# Ad_Hoc_Radio_Node_2005_v2.net
KiCad netlist of a schematic drawn in Altium Designer
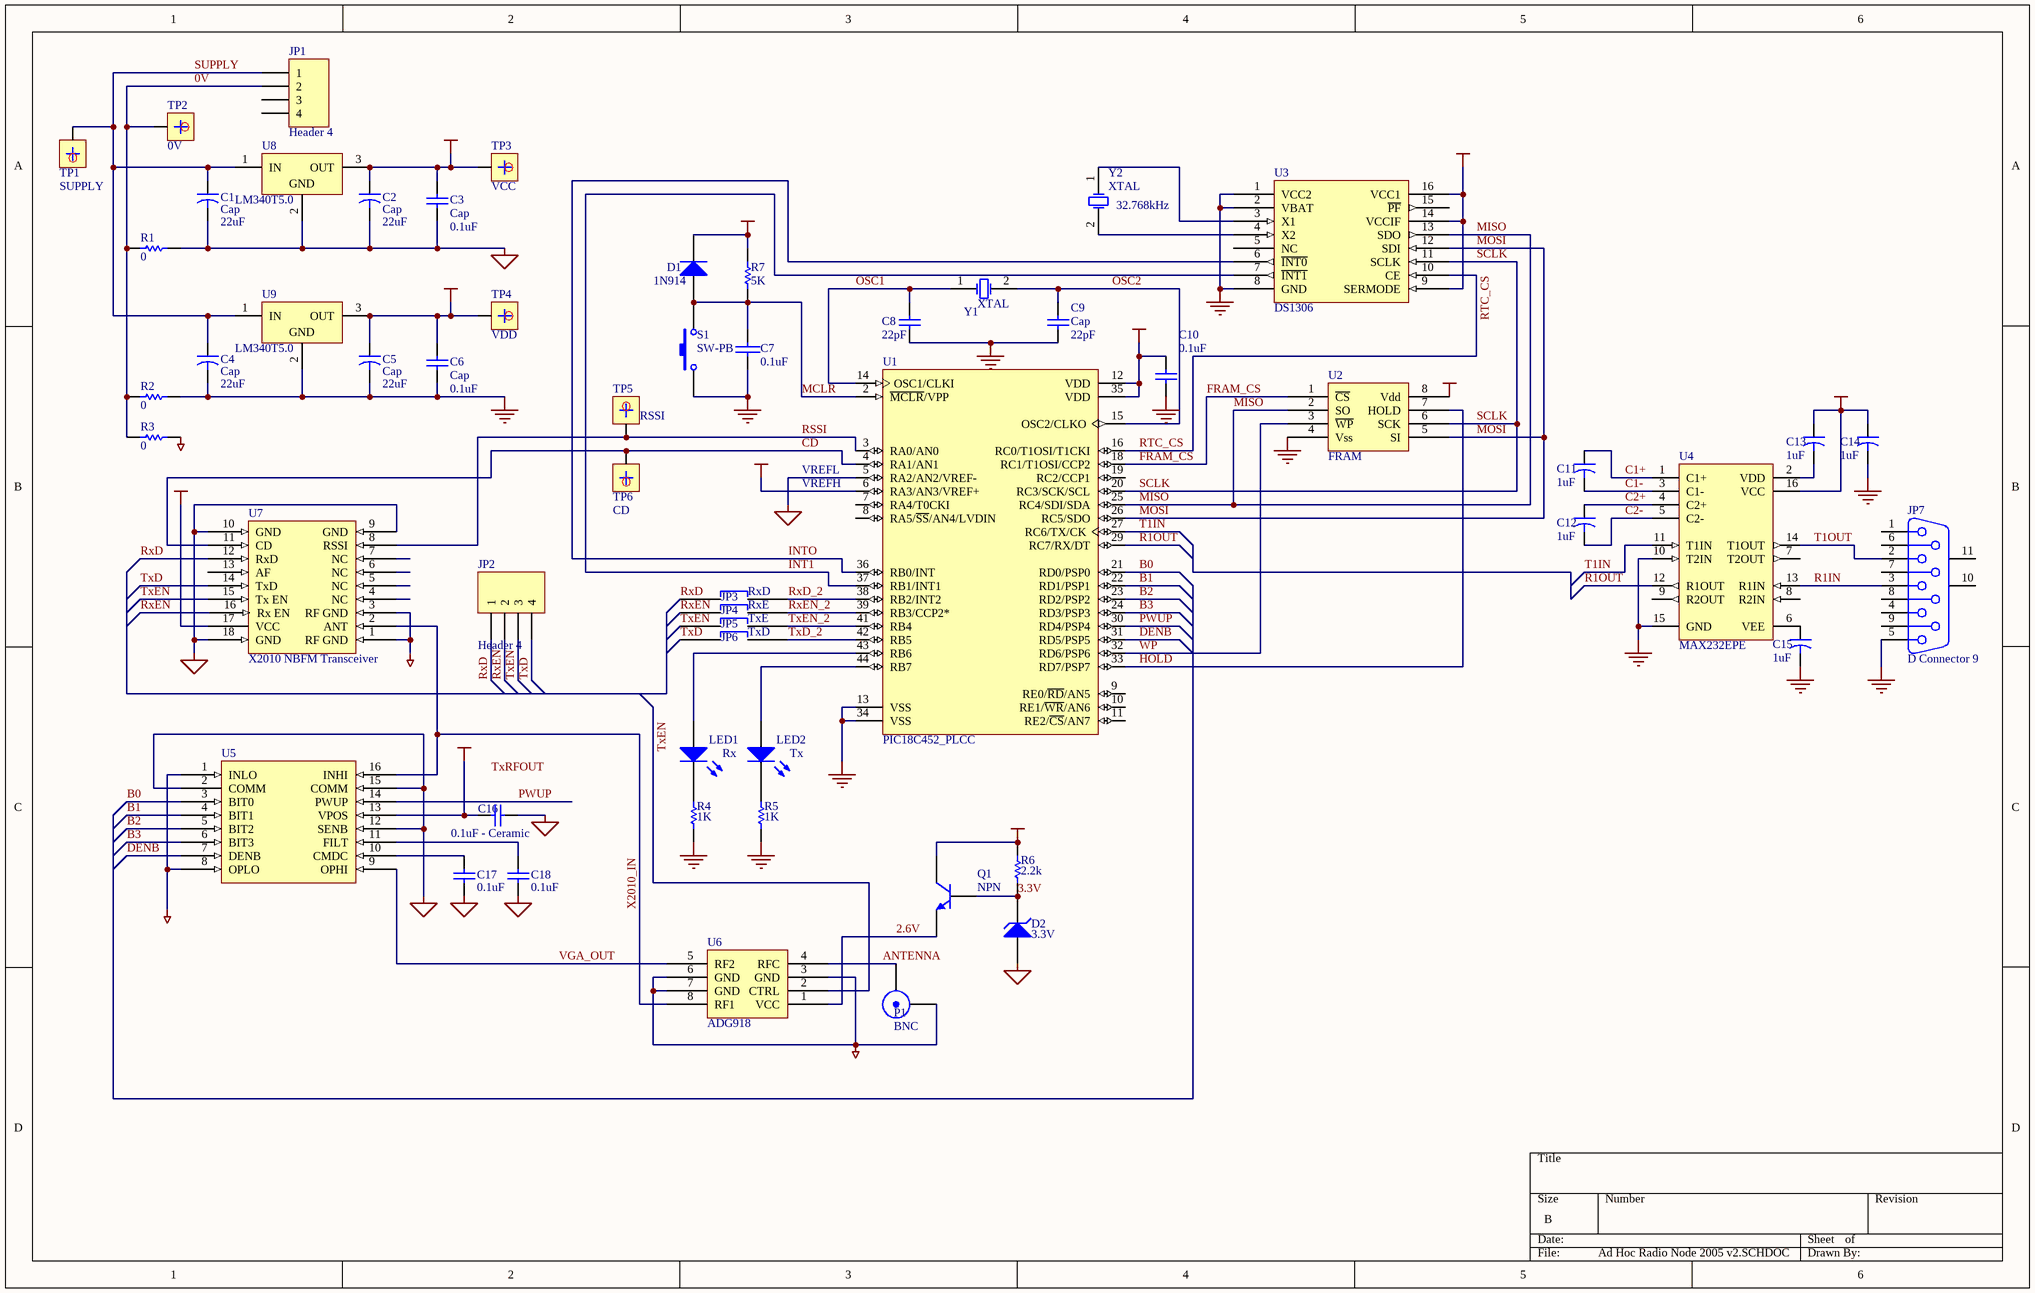
[diagram p0: Ad Hoc Radio Node 2005 v2.SCHDOC]

(export (version "E")
  (design (tool "Eeschema 10.0.6"))
  (components
    (comp (ref "C1")
      (value "Cap")
      (footprint "0.1 ELECTRO CAP")
      (description "Capacitor")
      (fields
        (field (name "MANUFACTURER") "Generic Components")
        (field (name "ALTIUM_VALUE") "22uF")
        (field (name "PUBLISHER") "Altium Limited")
      )
      (libsource (lib "Miscellaneous Devices") (part "Cap2"))
    )
    (comp (ref "C2")
      (value "Cap")
      (footprint "0.1 ELECTRO CAP")
      (description "Capacitor")
      (fields
        (field (name "MANUFACTURER") "Generic Components")
        (field (name "ALTIUM_VALUE") "22uF")
        (field (name "PUBLISHER") "Altium Limited")
      )
      (libsource (lib "Miscellaneous Devices") (part "Cap2"))
    )
    (comp (ref "C3")
      (value "Cap")
      (footprint "0.2 box cap")
      (description "Capacitor")
      (fields
        (field (name "MANUFACTURER") "Generic Components")
        (field (name "ALTIUM_VALUE") "0.1uF")
        (field (name "PUBLISHER") "Altium Limited")
      )
      (libsource (lib "Miscellaneous Devices") (part "Cap"))
    )
    (comp (ref "C4")
      (value "Cap")
      (footprint "0.1 RAD CAP")
      (description "Capacitor")
      (fields
        (field (name "MANUFACTURER") "Generic Components")
        (field (name "ALTIUM_VALUE") "22uF")
        (field (name "PUBLISHER") "Altium Limited")
      )
      (libsource (lib "Miscellaneous Devices") (part "Cap2"))
    )
    (comp (ref "C5")
      (value "Cap")
      (footprint "0.1 RAD CAP")
      (description "Capacitor")
      (fields
        (field (name "MANUFACTURER") "Generic Components")
        (field (name "ALTIUM_VALUE") "22uF")
        (field (name "PUBLISHER") "Altium Limited")
      )
      (libsource (lib "Miscellaneous Devices") (part "Cap2"))
    )
    (comp (ref "C6")
      (value "Cap")
      (footprint "0.2 box cap")
      (description "Capacitor")
      (fields
        (field (name "MANUFACTURER") "Generic Components")
        (field (name "ALTIUM_VALUE") "0.1uF")
        (field (name "PUBLISHER") "Altium Limited")
      )
      (libsource (lib "Miscellaneous Devices") (part "Cap"))
    )
    (comp (ref "C7")
      (value "0.1uF")
      (footprint "0.2 box cap")
      (description "Capacitor")
      (libsource (lib "*") (part "CAP"))
    )
    (comp (ref "C8")
      (value "Cap")
      (footprint "0.2 box cap")
      (description "Capacitor")
      (fields
        (field (name "MANUFACTURER") "Generic Components")
        (field (name "ALTIUM_VALUE") "22pF")
        (field (name "PUBLISHER") "Altium Limited")
      )
      (libsource (lib "Miscellaneous Devices") (part "Cap"))
    )
    (comp (ref "C9")
      (value "Cap")
      (footprint "0.2 box cap")
      (description "Capacitor")
      (fields
        (field (name "MANUFACTURER") "Generic Components")
        (field (name "ALTIUM_VALUE") "22pF")
        (field (name "PUBLISHER") "Altium Limited")
      )
      (libsource (lib "Miscellaneous Devices") (part "Cap"))
    )
    (comp (ref "C10")
      (value "0.1uF")
      (footprint "0.3 BOX CAP")
      (description "Capacitor")
      (fields (field (name "MANUFACTURER") "Generic Components") (field (name "PUBLISHER") "Altium Limited"))
      (libsource (lib "Miscellaneous Devices") (part "Cap"))
    )
    (comp (ref "C11")
      (value "Cap2")
      (footprint "0.1 RAD CAP")
      (description "Capacitor")
      (fields
        (field (name "MANUFACTURER") "Generic Components")
        (field (name "ALTIUM_VALUE") "1uF")
        (field (name "PUBLISHER") "Altium Limited")
      )
      (libsource (lib "Miscellaneous Devices") (part "Cap2"))
    )
    (comp (ref "C12")
      (value "Cap2")
      (footprint "0.1 RAD CAP")
      (description "Capacitor")
      (fields
        (field (name "MANUFACTURER") "Generic Components")
        (field (name "ALTIUM_VALUE") "1uF")
        (field (name "PUBLISHER") "Altium Limited")
      )
      (libsource (lib "Miscellaneous Devices") (part "Cap2"))
    )
    (comp (ref "C13")
      (value "Cap2")
      (footprint "0.1 RAD CAP")
      (description "Capacitor")
      (fields
        (field (name "MANUFACTURER") "Generic Components")
        (field (name "ALTIUM_VALUE") "1uF")
        (field (name "PUBLISHER") "Altium Limited")
      )
      (libsource (lib "Miscellaneous Devices") (part "Cap2"))
    )
    (comp (ref "C14")
      (value "Cap2")
      (footprint "0.1 RAD CAP")
      (description "Capacitor")
      (fields
        (field (name "MANUFACTURER") "Generic Components")
        (field (name "ALTIUM_VALUE") "1uF")
        (field (name "PUBLISHER") "Altium Limited")
      )
      (libsource (lib "Miscellaneous Devices") (part "Cap2"))
    )
    (comp (ref "C15")
      (value "Cap2")
      (footprint "0.1 RAD CAP")
      (description "Capacitor")
      (fields
        (field (name "MANUFACTURER") "Generic Components")
        (field (name "ALTIUM_VALUE") "1uF")
        (field (name "PUBLISHER") "Altium Limited")
      )
      (libsource (lib "Miscellaneous Devices") (part "Cap2"))
    )
    (comp (ref "C16")
      (value "0.1uF - Ceramic")
      (footprint "0.2 box cap")
      (description "Capacitor")
      (fields (field (name "MANUFACTURER") "Generic Components") (field (name "PUBLISHER") "Altium Limited"))
      (libsource (lib "Miscellaneous Devices") (part "Cap"))
    )
    (comp (ref "C17")
      (value "0.1uF")
      (footprint "0.2 box cap")
      (description "Capacitor")
      (fields (field (name "MANUFACTURER") "Generic Components") (field (name "PUBLISHER") "Altium Limited"))
      (libsource (lib "Miscellaneous Devices") (part "Cap"))
    )
    (comp (ref "C18")
      (value "0.1uF")
      (footprint "0.2 box cap")
      (description "Capacitor")
      (fields (field (name "MANUFACTURER") "Generic Components") (field (name "PUBLISHER") "Altium Limited"))
      (libsource (lib "Miscellaneous Devices") (part "Cap"))
    )
    (comp (ref "D1")
      (value "1N914")
      (footprint "diode-0.4/1.8")
      (description "Default Diode")
      (fields (field (name "MANUFACTURER") "Generic Components") (field (name "PUBLISHER") "Altium Limited"))
      (libsource (lib "Miscellaneous Devices") (part "Diode"))
    )
    (comp (ref "D2")
      (value "D Zener")
      (footprint "diode-0.4/1.8")
      (description "Zener Diode")
      (fields
        (field (name "MANUFACTURER") "Generic Components")
        (field (name "ALTIUM_VALUE") "3.3V")
        (field (name "PUBLISHER") "Altium Limited")
      )
      (libsource (lib "Miscellaneous Devices") (part "D Zener"))
    )
    (comp (ref "JP1")
      (value "Header 4")
      (footprint "4 Way Terminal Block")
      (description "Header, 4-Pin")
      (fields (field (name "MANUFACTURER") "Generic Components") (field (name "PUBLISHER") "Altium Limited"))
      (libsource (lib "Miscellaneous Connectors") (part "Header 4"))
    )
    (comp (ref "JP2")
      (value "Header 4")
      (footprint "4 Way Terminal Block")
      (description "Header, 4-Pin")
      (fields (field (name "MANUFACTURER") "Generic Components") (field (name "PUBLISHER") "Altium Limited"))
      (libsource (lib "") (part "Header 4_1"))
    )
    (comp (ref "JP3") (value "RxD") (footprint "JUMPER") (libsource (lib "2005Parts") (part "JUMPER")))
    (comp (ref "JP4") (value "RxE") (footprint "JUMPER") (libsource (lib "2005Parts") (part "JUMPER")))
    (comp (ref "JP5") (value "TxE") (footprint "JUMPER") (libsource (lib "2005Parts") (part "JUMPER")))
    (comp (ref "JP6") (value "TxD") (footprint "JUMPER") (libsource (lib "2005Parts") (part "JUMPER")))
    (comp (ref "JP7")
      (value "D Connector 9")
      (footprint "DSUB1.385-2H9")
      (description "Receptacle Assembly, 9 Position, Right Angle")
      (fields (field (name "MANUFACTURER") "Generic Components") (field (name "PUBLISHER") "Altium Limited"))
      (libsource (lib "Miscellaneous Connectors") (part "D Connector 9"))
    )
    (comp (ref "LED1")
      (value "Rx")
      (footprint "Std LED")
      (description "Typical RED, GREEN, YELLOW, AMBER GaAs LED")
      (fields (field (name "MANUFACTURER") "Generic Components") (field (name "PUBLISHER") "Altium Limited"))
      (libsource (lib "Miscellaneous Devices") (part "LED2"))
    )
    (comp (ref "LED2")
      (value "Tx")
      (footprint "Std LED")
      (description "Typical RED, GREEN, YELLOW, AMBER GaAs LED")
      (fields (field (name "MANUFACTURER") "Generic Components") (field (name "PUBLISHER") "Altium Limited"))
      (libsource (lib "Miscellaneous Devices") (part "LED2"))
    )
    (comp (ref "P1")
      (value "BNC")
      (footprint "PCB BNC Connector - duplicate")
      (description "BNC Elbow Connector")
      (fields (field (name "MANUFACTURER") "Generic Components") (field (name "PUBLISHER") "Altium Limited"))
      (libsource (lib "Miscellaneous Connectors") (part "BNC"))
    )
    (comp (ref "Q1")
      (value "NPN")
      (footprint "bjt")
      (description "NPN Bipolar Transistor")
      (fields (field (name "MANUFACTURER") "Generic Components") (field (name "PUBLISHER") "Altium Limited"))
      (libsource (lib "Miscellaneous Devices") (part "NPN"))
    )
    (comp (ref "R1")
      (value "0")
      (footprint "AXIAL-0.3")
      (description "Resistor")
      (fields (field (name "MANUFACTURER") "Generic Components") (field (name "PUBLISHER") "Altium Limited"))
      (libsource (lib "Miscellaneous Devices") (part "Res1"))
    )
    (comp (ref "R2")
      (value "0")
      (footprint "AXIAL-0.3")
      (description "Resistor")
      (fields (field (name "MANUFACTURER") "Generic Components") (field (name "PUBLISHER") "Altium Limited"))
      (libsource (lib "Miscellaneous Devices") (part "Res1"))
    )
    (comp (ref "R3")
      (value "0")
      (footprint "AXIAL-0.3")
      (description "Resistor")
      (fields (field (name "MANUFACTURER") "Generic Components") (field (name "PUBLISHER") "Altium Limited"))
      (libsource (lib "Miscellaneous Devices") (part "Res1"))
    )
    (comp (ref "R4")
      (value "1K")
      (footprint "AXIAL-0.4/1.8")
      (description "Resistor")
      (fields (field (name "MANUFACTURER") "Generic Components") (field (name "PUBLISHER") "Altium Limited"))
      (libsource (lib "Miscellaneous Devices") (part "Res1"))
    )
    (comp (ref "R5")
      (value "1K")
      (footprint "AXIAL-0.4/1.8")
      (description "Resistor")
      (fields (field (name "MANUFACTURER") "Generic Components") (field (name "PUBLISHER") "Altium Limited"))
      (libsource (lib "Miscellaneous Devices") (part "Res1"))
    )
    (comp (ref "R6")
      (value "2.2k")
      (footprint "AXIAL-0.4/1.8")
      (description "Resistor")
      (fields (field (name "MANUFACTURER") "Generic Components") (field (name "PUBLISHER") "Altium Limited"))
      (libsource (lib "Miscellaneous Devices") (part "Res1"))
    )
    (comp (ref "R7")
      (value "Res1")
      (footprint "AXIAL-0.4/1.8")
      (description "Resistor")
      (fields
        (field (name "MANUFACTURER") "Generic Components")
        (field (name "ALTIUM_VALUE") "5K")
        (field (name "PUBLISHER") "Altium Limited")
      )
      (libsource (lib "Miscellaneous Devices") (part "Res1"))
    )
    (comp (ref "S1")
      (value "SW-PB")
      (footprint "Reset Switch - duplicate")
      (description "Switch")
      (fields (field (name "MANUFACTURER") "Generic Components") (field (name "PUBLISHER") "Altium Limited"))
      (libsource (lib "Miscellaneous Devices") (part "SW-PB"))
    )
    (comp (ref "TP1")
      (value "SUPPLY")
      (footprint "TESTPOINT")
      (description "Test Point")
      (libsource (lib "PeteSchLib") (part "TESTPOINT"))
    )
    (comp (ref "TP2")
      (value "0V")
      (footprint "TESTPOINT")
      (description "Test Point")
      (libsource (lib "") (part "TESTPOINT_1"))
    )
    (comp (ref "TP3")
      (value "VCC")
      (footprint "TESTPOINT")
      (description "Test Point")
      (libsource (lib "") (part "TESTPOINT_1"))
    )
    (comp (ref "TP4")
      (value "VDD")
      (footprint "TESTPOINT")
      (description "Test Point")
      (libsource (lib "") (part "TESTPOINT_1"))
    )
    (comp (ref "TP5")
      (value "RSSI")
      (footprint "TESTPOINT")
      (description "Test Point")
      (libsource (lib "") (part "TESTPOINT_2"))
    )
    (comp (ref "TP6")
      (value "CD")
      (footprint "TESTPOINT")
      (description "Test Point")
      (libsource (lib "PeteSchLib") (part "TESTPOINT"))
    )
    (comp (ref "U1")
      (value "PIC18C452_PLCC")
      (footprint "PIC18C452_PLCC - duplicate")
      (libsource (lib "Ad_Hoc_Parts") (part "PIC18C452_PLCC"))
    )
    (comp (ref "U2") (value "FRAM") (footprint "Ramtron FRAM") (libsource (lib "Ad_Hoc_Parts") (part "FRAM")))
    (comp (ref "U3") (value "DS1306") (footprint "DIP-16") (libsource (lib "2005Parts") (part "DS1306")))
    (comp (ref "U4")
      (value "MAX232EPE")
      (footprint "DIP-16")
      (description "+5V Powered RS-232 Driver/Receiver")
      (fields (field (name "MANUFACTURER") "Maxim") (field (name "PUBLISHER") "Altium Limited"))
      (libsource (lib "Maxim Communication Transceiver") (part "MAX232EPE"))
    )
    (comp (ref "U5")
      (value "~")
      (footprint "DIP16-Adaptor")
      (libsource (lib "Ad_Hoc_Parts") (part "AD8369_DIGITAL_CONT_PWR_AMP"))
    )
    (comp (ref "U6") (value "ADG918") (footprint "DIP-8") (libsource (lib "2005Parts") (part "ADG918")))
    (comp (ref "U7")
      (value "X2010 NBFM Transceiver")
      (footprint "X2010")
      (libsource (lib "Ad_Hoc_Parts") (part "NBFM_TRANSCEIVER"))
    )
    (comp (ref "U8")
      (value "LM340T5.0")
      (footprint "SFM-T3/A4.7V")
      (description "Series 3-Terminal Positive Regulator")
      (fields
        (field (name "MANUFACTURER") "National Semiconductor")
        (field (name "PUBLISHER") "Altium Limited")
      )
      (libsource (lib "NSC Power Mgt Voltage Regulator") (part "LM340T5.0"))
    )
    (comp (ref "U9")
      (value "LM340T5.0")
      (footprint "SFM-T3/A4.7V")
      (description "Series 3-Terminal Positive Regulator")
      (fields
        (field (name "MANUFACTURER") "National Semiconductor")
        (field (name "PUBLISHER") "Altium Limited")
      )
      (libsource (lib "NSC Power Mgt Voltage Regulator") (part "LM340T5.0"))
    )
    (comp (ref "Y1")
      (value "XTAL")
      (footprint "XTAL")
      (description "Crystal Oscillator")
      (fields (field (name "MANUFACTURER") "Generic Components") (field (name "PUBLISHER") "Altium Limited"))
      (libsource (lib "Miscellaneous Devices") (part "XTAL"))
    )
    (comp (ref "Y2")
      (value "XTAL")
      (footprint "2005Parts:XTAL")
      (description "Crystal Oscillator")
      (fields
        (field (name "MANUFACTURER") "Generic Components")
        (field (name "ALTIUM_VALUE") "32.768kHz")
        (field (name "PUBLISHER") "Altium Limited")
      )
      (libsource (lib "Miscellaneous Devices") (part "XTAL"))
    )
  )
  (nets
    (net (code "1") (name "/0V") (class "Default")
      (node (ref "JP1") (pin "2") (pinfunction "2_2") (pintype "passive"))
      (node (ref "R1") (pin "1") (pinfunction "1_1") (pintype "passive"))
      (node (ref "R2") (pin "1") (pinfunction "1_1") (pintype "passive"))
      (node (ref "R3") (pin "1") (pinfunction "1_1") (pintype "passive"))
      (node (ref "TP2") (pin "1") (pinfunction "TP_1") (pintype "passive"))
    )
    (net (code "2") (name "/2.6V") (class "Default")
      (node (ref "Q1") (pin "3") (pinfunction "E_3") (pintype "passive"))
      (node (ref "U6") (pin "1") (pinfunction "VCC_1") (pintype "passive"))
    )
    (net (code "3") (name "/3.3V") (class "Default")
      (node (ref "D2") (pin "2") (pinfunction "K_2") (pintype "passive"))
      (node (ref "Q1") (pin "2") (pinfunction "B_2") (pintype "passive"))
      (node (ref "R6") (pin "2") (pinfunction "2_2") (pintype "passive"))
    )
    (net (code "4") (name "/ANTENNA") (class "Default")
      (node (ref "P1") (pin "1") (pinfunction "X_1") (pintype "passive"))
      (node (ref "U6") (pin "4") (pinfunction "RFC_4") (pintype "passive"))
    )
    (net (code "5") (name "/B0") (class "Default")
      (node (ref "U1") (pin "21") (pinfunction "RD0/PSP0_21") (pintype "bidirectional"))
      (node (ref "U5") (pin "3") (pinfunction "BIT0_3") (pintype "input"))
    )
    (net (code "6") (name "/B1") (class "Default")
      (node (ref "U1") (pin "22") (pinfunction "RD1/PSP1_22") (pintype "bidirectional"))
      (node (ref "U5") (pin "4") (pinfunction "BIT1_4") (pintype "input"))
    )
    (net (code "7") (name "/B2") (class "Default")
      (node (ref "U1") (pin "23") (pinfunction "RD2/PSP2_23") (pintype "bidirectional"))
      (node (ref "U5") (pin "5") (pinfunction "BIT2_5") (pintype "input"))
    )
    (net (code "8") (name "/B3") (class "Default")
      (node (ref "U1") (pin "24") (pinfunction "RD3/PSP3_24") (pintype "bidirectional"))
      (node (ref "U5") (pin "6") (pinfunction "BIT3_6") (pintype "input"))
    )
    (net (code "9") (name "/C1+") (class "Default")
      (node (ref "C11") (pin "1") (pinfunction "1_1") (pintype "passive"))
      (node (ref "U4") (pin "1") (pinfunction "C1+_1") (pintype "passive"))
    )
    (net (code "10") (name "/C1-") (class "Default")
      (node (ref "C11") (pin "2") (pinfunction "2_2") (pintype "passive"))
      (node (ref "U4") (pin "3") (pinfunction "C1-_3") (pintype "passive"))
    )
    (net (code "11") (name "/C2+") (class "Default")
      (node (ref "C12") (pin "1") (pinfunction "1_1") (pintype "passive"))
      (node (ref "U4") (pin "4") (pinfunction "C2+_4") (pintype "passive"))
    )
    (net (code "12") (name "/C2-") (class "Default")
      (node (ref "C12") (pin "2") (pinfunction "2_2") (pintype "passive"))
      (node (ref "U4") (pin "5") (pinfunction "C2-_5") (pintype "passive"))
    )
    (net (code "13") (name "/CD") (class "Default")
      (node (ref "TP6") (pin "1") (pinfunction "TP_1") (pintype "passive"))
      (node (ref "U1") (pin "4") (pinfunction "RA1/AN1_4") (pintype "bidirectional"))
      (node (ref "U7") (pin "11") (pinfunction "CD_11") (pintype "input"))
    )
    (net (code "14") (name "/DENB") (class "Default")
      (node (ref "U1") (pin "31") (pinfunction "RD5/PSP5_31") (pintype "bidirectional"))
      (node (ref "U5") (pin "7") (pinfunction "DENB_7") (pintype "input"))
    )
    (net (code "15") (name "/FRAM_CS") (class "Default")
      (node (ref "U1") (pin "18") (pinfunction "RC1/T1OSI/CCP2_18") (pintype "bidirectional"))
      (node (ref "U2") (pin "1") (pinfunction "~{CS}_1") (pintype "passive"))
    )
    (net (code "16") (name "/HOLD") (class "Default")
      (node (ref "U1") (pin "33") (pinfunction "RD7/PSP7_33") (pintype "bidirectional"))
      (node (ref "U2") (pin "7") (pinfunction "HOLD_7") (pintype "passive"))
    )
    (net (code "17") (name "/INT1") (class "Default")
      (node (ref "U1") (pin "37") (pinfunction "RB1/INT1_37") (pintype "bidirectional"))
      (node (ref "U3") (pin "7") (pinfunction "~{INT1}_7") (pintype "output"))
    )
    (net (code "18") (name "/INTO") (class "Default")
      (node (ref "U1") (pin "36") (pinfunction "RB0/INT_36") (pintype "bidirectional"))
      (node (ref "U3") (pin "6") (pinfunction "~{INT0}_6") (pintype "output"))
    )
    (net (code "19") (name "/MCLR") (class "Default")
      (node (ref "C7") (pin "1") (pinfunction "1_1") (pintype "passive"))
      (node (ref "D1") (pin "1") (pinfunction "A_1") (pintype "passive"))
      (node (ref "R7") (pin "1") (pinfunction "1_1") (pintype "passive"))
      (node (ref "S1") (pin "2") (pinfunction "2_2") (pintype "passive"))
      (node (ref "U1") (pin "2") (pinfunction "~{MCLR}/VPP_2") (pintype "input"))
    )
    (net (code "20") (name "/MISO") (class "Default")
      (node (ref "U1") (pin "25") (pinfunction "RC4/SDI/SDA_25") (pintype "bidirectional"))
      (node (ref "U2") (pin "2") (pinfunction "SO_2") (pintype "passive"))
      (node (ref "U3") (pin "13") (pinfunction "SDO_13") (pintype "output"))
    )
    (net (code "21") (name "/MOSI") (class "Default")
      (node (ref "U1") (pin "26") (pinfunction "RC5/SDO_26") (pintype "bidirectional"))
      (node (ref "U2") (pin "5") (pinfunction "SI_5") (pintype "passive"))
      (node (ref "U3") (pin "12") (pinfunction "SDI_12") (pintype "input"))
    )
    (net (code "22") (name "/OSC1") (class "Default")
      (node (ref "C8") (pin "2") (pinfunction "2_2") (pintype "passive"))
      (node (ref "U1") (pin "14") (pinfunction "OSC1/CLKI_14") (pintype "input"))
      (node (ref "Y1") (pin "1") (pinfunction "OSC1_1") (pintype "passive"))
    )
    (net (code "23") (name "/OSC2") (class "Default")
      (node (ref "C9") (pin "2") (pinfunction "2_2") (pintype "passive"))
      (node (ref "U1") (pin "15") (pinfunction "OSC2/CLKO_15") (pintype "output"))
      (node (ref "Y1") (pin "2") (pinfunction "OSC2_2") (pintype "passive"))
    )
    (net (code "24") (name "/PWUP") (class "Default")
      (node (ref "U1") (pin "30") (pinfunction "RD4/PSP4_30") (pintype "bidirectional"))
      (node (ref "U5") (pin "14") (pinfunction "PWUP_14") (pintype "input"))
    )
    (net (code "25") (name "/R1IN") (class "Default")
      (node (ref "JP7") (pin "3") (pinfunction "3_3") (pintype "passive"))
      (node (ref "U4") (pin "13") (pinfunction "R1IN_13") (pintype "input"))
    )
    (net (code "26") (name "/R1OUT") (class "Default")
      (node (ref "U1") (pin "29") (pinfunction "RC7/RX/DT_29") (pintype "bidirectional"))
      (node (ref "U4") (pin "12") (pinfunction "R1OUT_12") (pintype "output"))
    )
    (net (code "27") (name "/RSSI") (class "Default")
      (node (ref "TP5") (pin "1") (pinfunction "TP_1") (pintype "passive"))
      (node (ref "U1") (pin "3") (pinfunction "RA0/AN0_3") (pintype "bidirectional"))
      (node (ref "U7") (pin "8") (pinfunction "RSSI_8") (pintype "input"))
    )
    (net (code "28") (name "/RTC_CS") (class "Default")
      (node (ref "U1") (pin "16") (pinfunction "RC0/T1OSI/T1CKI_16") (pintype "bidirectional"))
      (node (ref "U3") (pin "10") (pinfunction "CE_10") (pintype "input"))
    )
    (net (code "29") (name "/RxD") (class "Default")
      (node (ref "JP2") (pin "1") (pinfunction "1_1") (pintype "passive"))
      (node (ref "JP3") (pin "1") (pinfunction "1_1") (pintype "passive"))
      (node (ref "U7") (pin "12") (pinfunction "RxD_12") (pintype "input"))
    )
    (net (code "30") (name "/RxD_2") (class "Default")
      (node (ref "JP3") (pin "2") (pinfunction "2_2") (pintype "passive"))
      (node (ref "U1") (pin "38") (pinfunction "RB2/INT2_38") (pintype "bidirectional"))
    )
    (net (code "31") (name "/RxEN") (class "Default")
      (node (ref "JP2") (pin "2") (pinfunction "2_2") (pintype "passive"))
      (node (ref "JP4") (pin "1") (pinfunction "1_1") (pintype "passive"))
      (node (ref "U7") (pin "16") (pinfunction "Rx_EN_16") (pintype "input"))
    )
    (net (code "32") (name "/RxEN_2") (class "Default")
      (node (ref "JP4") (pin "2") (pinfunction "2_2") (pintype "passive"))
      (node (ref "U1") (pin "39") (pinfunction "RB3/CCP2*_39") (pintype "bidirectional"))
    )
    (net (code "33") (name "/SCLK") (class "Default")
      (node (ref "U1") (pin "20") (pinfunction "RC3/SCK/SCL_20") (pintype "bidirectional"))
      (node (ref "U2") (pin "6") (pinfunction "SCK_6") (pintype "passive"))
      (node (ref "U3") (pin "11") (pinfunction "SCLK_11") (pintype "input"))
    )
    (net (code "34") (name "/SUPPLY") (class "Default")
      (node (ref "C1") (pin "1") (pinfunction "1_1") (pintype "passive"))
      (node (ref "C4") (pin "1") (pinfunction "1_1") (pintype "passive"))
      (node (ref "JP1") (pin "1") (pinfunction "1_1") (pintype "passive"))
      (node (ref "TP1") (pin "1") (pinfunction "TP_1") (pintype "passive"))
      (node (ref "U8") (pin "1") (pinfunction "IN_1") (pintype "power_in"))
      (node (ref "U9") (pin "1") (pinfunction "IN_1") (pintype "power_in"))
    )
    (net (code "35") (name "/T1IN") (class "Default")
      (node (ref "U1") (pin "27") (pinfunction "RC6/TX/CK_27") (pintype "bidirectional"))
      (node (ref "U4") (pin "11") (pinfunction "T1IN_11") (pintype "input"))
    )
    (net (code "36") (name "/T1OUT") (class "Default")
      (node (ref "JP7") (pin "2") (pinfunction "2_2") (pintype "passive"))
      (node (ref "U4") (pin "14") (pinfunction "T1OUT_14") (pintype "output"))
    )
    (net (code "37") (name "/TxD") (class "Default")
      (node (ref "JP2") (pin "4") (pinfunction "4_4") (pintype "passive"))
      (node (ref "JP6") (pin "1") (pinfunction "1_1") (pintype "passive"))
      (node (ref "U7") (pin "14") (pinfunction "TxD_14") (pintype "input"))
    )
    (net (code "38") (name "/TxD_2") (class "Default")
      (node (ref "JP6") (pin "2") (pinfunction "2_2") (pintype "passive"))
      (node (ref "U1") (pin "42") (pinfunction "RB5_42") (pintype "bidirectional"))
    )
    (net (code "39") (name "/TxEN") (class "Default")
      (node (ref "JP2") (pin "3") (pinfunction "3_3") (pintype "passive"))
      (node (ref "JP5") (pin "1") (pinfunction "1_1") (pintype "passive"))
      (node (ref "U6") (pin "2") (pinfunction "CTRL_2") (pintype "passive"))
      (node (ref "U7") (pin "15") (pinfunction "Tx_EN_15") (pintype "input"))
    )
    (net (code "40") (name "/TxEN_2") (class "Default")
      (node (ref "JP5") (pin "2") (pinfunction "2_2") (pintype "passive"))
      (node (ref "U1") (pin "41") (pinfunction "RB4_41") (pintype "bidirectional"))
    )
    (net (code "42") (name "/VGA_OUT") (class "Default")
      (node (ref "U5") (pin "9") (pinfunction "OPHI_9") (pintype "input"))
      (node (ref "U6") (pin "5") (pinfunction "RF2_5") (pintype "passive"))
    )
    (net (code "43") (name "/WP") (class "Default")
      (node (ref "U1") (pin "32") (pinfunction "RD6/PSP6_32") (pintype "bidirectional"))
      (node (ref "U2") (pin "3") (pinfunction "~{WP}_3") (pintype "passive"))
    )
    (net (code "44") (name "/X2010_IN") (class "Default")
      (node (ref "U5") (pin "16") (pinfunction "INHI_16") (pintype "input"))
      (node (ref "U6") (pin "8") (pinfunction "RF1_8") (pintype "passive"))
      (node (ref "U7") (pin "2") (pinfunction "ANT_2") (pintype "input"))
    )
    (net (code "45") (name "GND") (class "Default")
      (node (ref "C10") (pin "2") (pinfunction "2_2") (pintype "passive"))
      (node (ref "C14") (pin "2") (pinfunction "2_2") (pintype "passive"))
      (node (ref "C15") (pin "2") (pinfunction "2_2") (pintype "passive"))
      (node (ref "C4") (pin "2") (pinfunction "2_2") (pintype "passive"))
      (node (ref "C5") (pin "2") (pinfunction "2_2") (pintype "passive"))
      (node (ref "C6") (pin "2") (pinfunction "2_2") (pintype "passive"))
      (node (ref "C7") (pin "2") (pinfunction "2_2") (pintype "passive"))
      (node (ref "C8") (pin "1") (pinfunction "1_1") (pintype "passive"))
      (node (ref "C9") (pin "1") (pinfunction "1_1") (pintype "passive"))
      (node (ref "JP7") (pin "5") (pinfunction "5_5") (pintype "passive"))
      (node (ref "R2") (pin "2") (pinfunction "2_2") (pintype "passive"))
      (node (ref "R4") (pin "2") (pinfunction "2_2") (pintype "passive"))
      (node (ref "R5") (pin "2") (pinfunction "2_2") (pintype "passive"))
      (node (ref "S1") (pin "1") (pinfunction "1_1") (pintype "passive"))
      (node (ref "U1") (pin "13") (pinfunction "VSS_13") (pintype "power_in"))
      (node (ref "U1") (pin "34") (pinfunction "VSS_34") (pintype "power_in"))
      (node (ref "U2") (pin "4") (pinfunction "Vss_4") (pintype "passive"))
      (node (ref "U3") (pin "1") (pinfunction "VCC2_1") (pintype "power_in"))
      (node (ref "U3") (pin "2") (pinfunction "VBAT_2") (pintype "power_in"))
      (node (ref "U3") (pin "8") (pinfunction "GND_8") (pintype "power_in"))
      (node (ref "U4") (pin "10") (pinfunction "T2IN_10") (pintype "input"))
      (node (ref "U4") (pin "15") (pinfunction "GND_15") (pintype "power_in"))
      (node (ref "U9") (pin "2") (pinfunction "GND_2") (pintype "power_in"))
    )
    (net (code "46") (name "Net-(LED1-A)") (class "Default")
      (node (ref "LED1") (pin "1") (pinfunction "A_1") (pintype "passive"))
      (node (ref "U1") (pin "43") (pinfunction "RB6_43") (pintype "bidirectional"))
    )
    (net (code "47") (name "Net-(LED1-K)") (class "Default")
      (node (ref "LED1") (pin "2") (pinfunction "K_2") (pintype "passive"))
      (node (ref "R4") (pin "1") (pinfunction "1_1") (pintype "passive"))
    )
    (net (code "48") (name "Net-(LED2-A)") (class "Default")
      (node (ref "LED2") (pin "1") (pinfunction "A_1") (pintype "passive"))
      (node (ref "U1") (pin "44") (pinfunction "RB7_44") (pintype "bidirectional"))
    )
    (net (code "49") (name "Net-(LED2-K)") (class "Default")
      (node (ref "LED2") (pin "2") (pinfunction "K_2") (pintype "passive"))
      (node (ref "R5") (pin "1") (pinfunction "1_1") (pintype "passive"))
    )
    (net (code "50") (name "Net-(U3-X1)") (class "Default")
      (node (ref "U3") (pin "3") (pinfunction "X1_3") (pintype "input"))
      (node (ref "Y2") (pin "1") (pinfunction "OSC1_1") (pintype "passive"))
    )
    (net (code "51") (name "Net-(U3-X2)") (class "Default")
      (node (ref "U3") (pin "4") (pinfunction "X2_4") (pintype "input"))
      (node (ref "Y2") (pin "2") (pinfunction "OSC2_2") (pintype "passive"))
    )
    (net (code "52") (name "Net-(U4-VDD)") (class "Default")
      (node (ref "C13") (pin "2") (pinfunction "2_2") (pintype "passive"))
      (node (ref "U4") (pin "2") (pinfunction "VDD_2") (pintype "power_in"))
    )
    (net (code "53") (name "Net-(U4-VEE)") (class "Default")
      (node (ref "C15") (pin "1") (pinfunction "1_1") (pintype "passive"))
      (node (ref "U4") (pin "6") (pinfunction "VEE_6") (pintype "power_in"))
    )
    (net (code "54") (name "Net-(U5-CMDC)") (class "Default")
      (node (ref "C17") (pin "1") (pinfunction "1_1") (pintype "passive"))
      (node (ref "U5") (pin "10") (pinfunction "CMDC_10") (pintype "input"))
    )
    (net (code "55") (name "Net-(U5-FILT)") (class "Default")
      (node (ref "C18") (pin "1") (pinfunction "1_1") (pintype "passive"))
      (node (ref "U5") (pin "11") (pinfunction "FILT_11") (pintype "input"))
    )
    (net (code "56") (name "RFGND") (class "Default")
      (node (ref "P1") (pin "2") (pinfunction "Y_2") (pintype "passive"))
      (node (ref "R3") (pin "2") (pinfunction "2_2") (pintype "passive"))
      (node (ref "U5") (pin "1") (pinfunction "INLO_1") (pintype "input"))
      (node (ref "U5") (pin "8") (pinfunction "OPLO_8") (pintype "input"))
      (node (ref "U6") (pin "3") (pinfunction "GND_3") (pintype "passive"))
      (node (ref "U6") (pin "6") (pinfunction "GND_6") (pintype "passive"))
      (node (ref "U6") (pin "7") (pinfunction "GND_7") (pintype "passive"))
      (node (ref "U7") (pin "1") (pinfunction "RF_GND_1") (pintype "input"))
      (node (ref "U7") (pin "3") (pinfunction "RF_GND_3") (pintype "input"))
    )
    (net (code "57") (name "SGND") (class "Default")
      (node (ref "C1") (pin "2") (pinfunction "2_2") (pintype "passive"))
      (node (ref "C16") (pin "1") (pinfunction "1_1") (pintype "passive"))
      (node (ref "C17") (pin "2") (pinfunction "2_2") (pintype "passive"))
      (node (ref "C18") (pin "2") (pinfunction "2_2") (pintype "passive"))
      (node (ref "C2") (pin "2") (pinfunction "2_2") (pintype "passive"))
      (node (ref "C3") (pin "2") (pinfunction "2_2") (pintype "passive"))
      (node (ref "D2") (pin "1") (pinfunction "A_1") (pintype "passive"))
      (node (ref "R1") (pin "2") (pinfunction "2_2") (pintype "passive"))
      (node (ref "U1") (pin "5") (pinfunction "RA2/AN2/VREF-_5") (pintype "bidirectional"))
      (node (ref "U5") (pin "12") (pinfunction "SENB_12") (pintype "input"))
      (node (ref "U5") (pin "15") (pinfunction "COMM_15") (pintype "input"))
      (node (ref "U5") (pin "2") (pinfunction "COMM_2") (pintype "power_in"))
      (node (ref "U7") (pin "10") (pinfunction "GND_10") (pintype "input"))
      (node (ref "U7") (pin "18") (pinfunction "GND_18") (pintype "input"))
      (node (ref "U7") (pin "9") (pinfunction "GND_9") (pintype "input"))
      (node (ref "U8") (pin "2") (pinfunction "GND_2") (pintype "power_in"))
    )
    (net (code "58") (name "VCC") (class "Default")
      (node (ref "C16") (pin "2") (pinfunction "2_2") (pintype "passive"))
      (node (ref "C2") (pin "1") (pinfunction "1_1") (pintype "passive"))
      (node (ref "C3") (pin "1") (pinfunction "1_1") (pintype "passive"))
      (node (ref "Q1") (pin "1") (pinfunction "C_1") (pintype "passive"))
      (node (ref "R6") (pin "1") (pinfunction "1_1") (pintype "passive"))
      (node (ref "TP3") (pin "1") (pinfunction "TP_1") (pintype "passive"))
      (node (ref "U1") (pin "6") (pinfunction "RA3/AN3/VREF+_6") (pintype "bidirectional"))
      (node (ref "U5") (pin "13") (pinfunction "VPOS_13") (pintype "input"))
      (node (ref "U7") (pin "17") (pinfunction "VCC_17") (pintype "power_in"))
      (node (ref "U8") (pin "3") (pinfunction "OUT_3") (pintype "power_in"))
    )
    (net (code "59") (name "VDD") (class "Default")
      (node (ref "C10") (pin "1") (pinfunction "1_1") (pintype "passive"))
      (node (ref "C13") (pin "1") (pinfunction "1_1") (pintype "passive"))
      (node (ref "C14") (pin "1") (pinfunction "1_1") (pintype "passive"))
      (node (ref "C5") (pin "1") (pinfunction "1_1") (pintype "passive"))
      (node (ref "C6") (pin "1") (pinfunction "1_1") (pintype "passive"))
      (node (ref "D1") (pin "2") (pinfunction "K_2") (pintype "passive"))
      (node (ref "R7") (pin "2") (pinfunction "2_2") (pintype "passive"))
      (node (ref "TP4") (pin "1") (pinfunction "TP_1") (pintype "passive"))
      (node (ref "U1") (pin "12") (pinfunction "VDD_12") (pintype "power_in"))
      (node (ref "U1") (pin "35") (pinfunction "VDD_35") (pintype "power_in"))
      (node (ref "U2") (pin "8") (pinfunction "Vdd_8") (pintype "passive"))
      (node (ref "U3") (pin "14") (pinfunction "VCCIF_14") (pintype "power_in"))
      (node (ref "U3") (pin "16") (pinfunction "VCC1_16") (pintype "power_in"))
      (node (ref "U3") (pin "9") (pinfunction "SERMODE_9") (pintype "input"))
      (node (ref "U4") (pin "16") (pinfunction "VCC_16") (pintype "power_in"))
      (node (ref "U9") (pin "3") (pinfunction "OUT_3") (pintype "power_in"))
    )
    (net (code "60") (name "unconnected-(JP1-Pad3)") (class "Default")
      (node (ref "JP1") (pin "3") (pinfunction "3_3") (pintype "passive"))
    )
    (net (code "61") (name "unconnected-(JP1-Pad4)") (class "Default")
      (node (ref "JP1") (pin "4") (pinfunction "4_4") (pintype "passive"))
    )
    (net (code "62") (name "unconnected-(JP7-MH1-Pad10)") (class "Default")
      (node (ref "JP7") (pin "10") (pinfunction "MH1_10") (pintype "passive"))
    )
    (net (code "63") (name "unconnected-(JP7-MH2-Pad11)") (class "Default")
      (node (ref "JP7") (pin "11") (pinfunction "MH2_11") (pintype "passive"))
    )
    (net (code "64") (name "unconnected-(JP7-Pad1)") (class "Default")
      (node (ref "JP7") (pin "1") (pinfunction "1_1") (pintype "passive"))
    )
    (net (code "65") (name "unconnected-(JP7-Pad4)") (class "Default")
      (node (ref "JP7") (pin "4") (pinfunction "4_4") (pintype "passive"))
    )
    (net (code "66") (name "unconnected-(JP7-Pad6)") (class "Default")
      (node (ref "JP7") (pin "6") (pinfunction "6_6") (pintype "passive"))
    )
    (net (code "67") (name "unconnected-(JP7-Pad7)") (class "Default")
      (node (ref "JP7") (pin "7") (pinfunction "7_7") (pintype "passive"))
    )
    (net (code "68") (name "unconnected-(JP7-Pad8)") (class "Default")
      (node (ref "JP7") (pin "8") (pinfunction "8_8") (pintype "passive"))
    )
    (net (code "69") (name "unconnected-(JP7-Pad9)") (class "Default")
      (node (ref "JP7") (pin "9") (pinfunction "9_9") (pintype "passive"))
    )
    (net (code "70") (name "unconnected-(U1-RA4{slash}T0CKI-Pad7)") (class "Default")
      (node (ref "U1") (pin "7") (pinfunction "RA4/T0CKI_7") (pintype "bidirectional"))
    )
    (net (code "71") (name "unconnected-(U1-RA5{slash}~{SS}{slash}AN4{slash}LVDIN-Pad8)") (class "Default")
      (node (ref "U1") (pin "8") (pinfunction "RA5/~{SS}/AN4/LVDIN_8") (pintype "bidirectional"))
    )
    (net (code "72") (name "unconnected-(U1-RC2{slash}CCP1-Pad19)") (class "Default")
      (node (ref "U1") (pin "19") (pinfunction "RC2/CCP1_19") (pintype "bidirectional"))
    )
    (net (code "73") (name "unconnected-(U1-RE0{slash}~{RD}{slash}AN5-Pad9)") (class "Default")
      (node (ref "U1") (pin "9") (pinfunction "RE0/~{RD}/AN5_9") (pintype "bidirectional"))
    )
    (net (code "74") (name "unconnected-(U1-RE1{slash}~{WR}{slash}AN6-Pad10)") (class "Default")
      (node (ref "U1") (pin "10") (pinfunction "RE1/~{WR}/AN6_10") (pintype "bidirectional"))
    )
    (net (code "75") (name "unconnected-(U1-RE2{slash}~{CS}{slash}AN7-Pad11)") (class "Default")
      (node (ref "U1") (pin "11") (pinfunction "RE2/~{CS}/AN7_11") (pintype "bidirectional"))
    )
    (net (code "76") (name "unconnected-(U3-NC-Pad5)") (class "Default")
      (node (ref "U3") (pin "5") (pinfunction "NC_5") (pintype "passive"))
    )
    (net (code "77") (name "unconnected-(U3-~{PF}-Pad15)") (class "Default")
      (node (ref "U3") (pin "15") (pinfunction "~{PF}_15") (pintype "output"))
    )
    (net (code "78") (name "unconnected-(U4-R2IN-Pad8)") (class "Default")
      (node (ref "U4") (pin "8") (pinfunction "R2IN_8") (pintype "input"))
    )
    (net (code "79") (name "unconnected-(U4-R2OUT-Pad9)") (class "Default")
      (node (ref "U4") (pin "9") (pinfunction "R2OUT_9") (pintype "output"))
    )
    (net (code "80") (name "unconnected-(U4-T2OUT-Pad7)") (class "Default")
      (node (ref "U4") (pin "7") (pinfunction "T2OUT_7") (pintype "output"))
    )
    (net (code "81") (name "unconnected-(U7-AF-Pad13)") (class "Default")
      (node (ref "U7") (pin "13") (pinfunction "AF_13") (pintype "input"))
    )
    (net (code "82") (name "unconnected-(U7-NC-Pad4)") (class "Default")
      (node (ref "U7") (pin "4") (pinfunction "NC_4") (pintype "input"))
    )
    (net (code "83") (name "unconnected-(U7-NC-Pad5)") (class "Default")
      (node (ref "U7") (pin "5") (pinfunction "NC_5") (pintype "input"))
    )
    (net (code "84") (name "unconnected-(U7-NC-Pad6)") (class "Default")
      (node (ref "U7") (pin "6") (pinfunction "NC_6") (pintype "input"))
    )
    (net (code "85") (name "unconnected-(U7-NC-Pad7)") (class "Default")
      (node (ref "U7") (pin "7") (pinfunction "NC_7") (pintype "input"))
    )
  )
)
